# Crystal_32_768kHz.net
KiCad netlist of a schematic drawn in Altium Designer
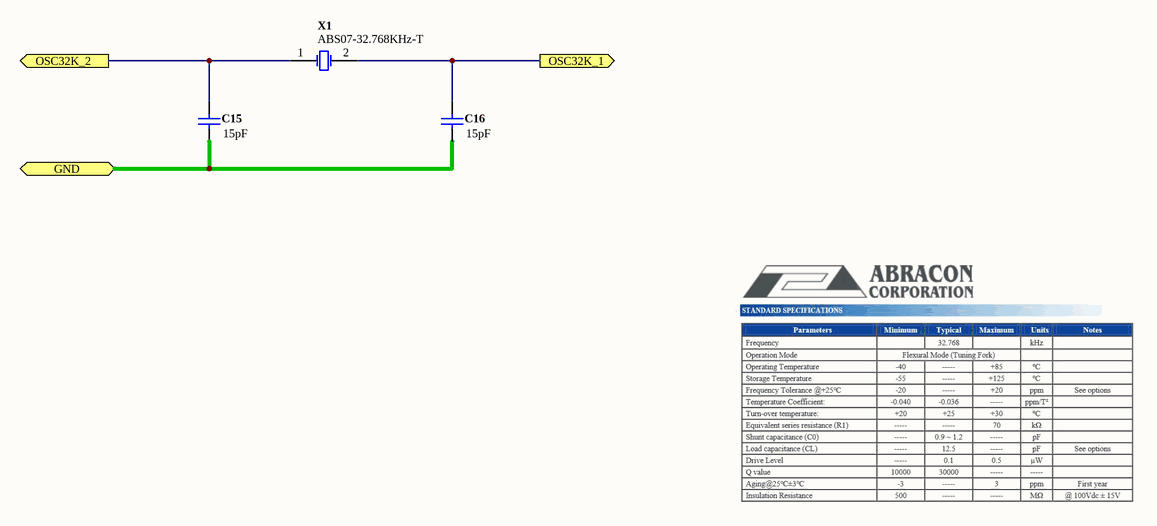
[diagram p0: Crystal_32.768kHz.SchDoc]

(export (version "E")
  (design (tool "Eeschema 10.0.6"))
  (components
    (comp (ref "C15")
      (value "15pF")
      (footprint "CAPC0402(1005)60_L")
      (description "CAP 15pF 16V ±1% 0402 (1005 Metric) Thickness 0.6mm SMD")
      (fields (field (name "TOLERANCE") "±1%") (field (name "Comment") "CAP 15pF 16V 0402(1005)"))
      (libsource (lib "Altium Content Vault") (part "CMP-1034-00800-1"))
    )
    (comp (ref "C16")
      (value "15pF")
      (footprint "CAPC0402(1005)60_L")
      (description "CAP 15pF 16V ±1% 0402 (1005 Metric) Thickness 0.6mm SMD")
      (fields (field (name "TOLERANCE") "±1%") (field (name "Comment") "CAP 15pF 16V 0402(1005)"))
      (libsource (lib "Altium Content Vault") (part "CMP-1034-00800-1"))
    )
    (comp (ref "X1")
      (value "ABS07-32.768KHz-T")
      (footprint "ABRA-ABS07-2_V")
      (description "Crystal, 32.768 kHz, 12.5 pF, -40 to 85 degC, SMD Low Profile 3.2 x 1.5 x 0.9 mm, Tape and Reel")
      (fields (field (name "MANUFACTURER") "Abracon"))
      (libsource (lib "Altium Content Vault") (part "CMP-0447-00001-1"))
    )
  )
  (nets
    (net (code "1") (name "/GND") (class "Default")
      (node (ref "C15") (pin "1") (pinfunction "1_1") (pintype "passive"))
      (node (ref "C16") (pin "1") (pinfunction "1_1") (pintype "passive"))
    )
    (net (code "2") (name "/OSC32K_1") (class "Default")
      (node (ref "C16") (pin "2") (pinfunction "2_2") (pintype "passive"))
      (node (ref "X1") (pin "2") (pinfunction "X2_2") (pintype "passive"))
    )
    (net (code "3") (name "/OSC32K_2") (class "Default")
      (node (ref "C15") (pin "2") (pinfunction "2_2") (pintype "passive"))
      (node (ref "X1") (pin "1") (pinfunction "X1_1") (pintype "passive"))
    )
  )
)
